# MBUSadapter.net
KiCad netlist of a schematic drawn in EAGLE
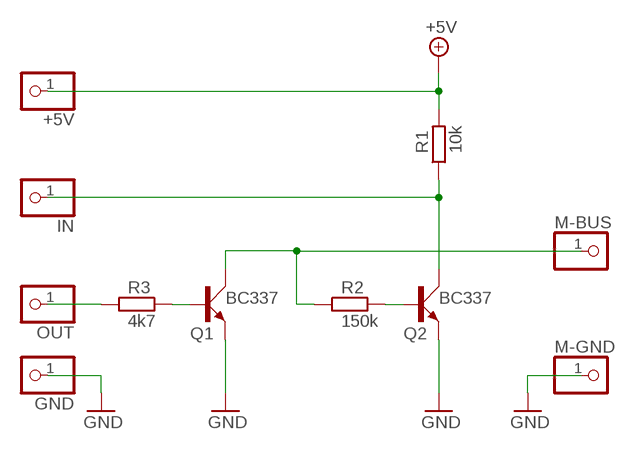
[diagram p0: schematic, sheet 1]

(export (version "E")
  (design (tool "Eeschema 10.0.6"))
  (components
    (comp (ref "+5V")
      (value "PINHD-1X1")
      (footprint "eagle-import:1X01")
      (libsource (lib "eagle-import") (part "PINHD-1X1"))
    )
    (comp (ref "GND")
      (value "PINHD-1X1")
      (footprint "eagle-import:1X01")
      (libsource (lib "eagle-import") (part "PINHD-1X1"))
    )
    (comp (ref "IN")
      (value "PINHD-1X1")
      (footprint "eagle-import:1X01")
      (libsource (lib "eagle-import") (part "PINHD-1X1"))
    )
    (comp (ref "M-BUS")
      (value "PINHD-1X1")
      (footprint "eagle-import:1X01")
      (libsource (lib "eagle-import") (part "PINHD-1X1"))
    )
    (comp (ref "M-GND")
      (value "PINHD-1X1")
      (footprint "eagle-import:1X01")
      (libsource (lib "eagle-import") (part "PINHD-1X1"))
    )
    (comp (ref "OUT")
      (value "PINHD-1X1")
      (footprint "eagle-import:1X01")
      (libsource (lib "eagle-import") (part "PINHD-1X1"))
    )
    (comp (ref "Q1")
      (value "BC337")
      (footprint "eagle-import:SOT54A")
      (libsource (lib "eagle-import") (part "BC337"))
    )
    (comp (ref "Q2")
      (value "BC337")
      (footprint "eagle-import:SOT54A")
      (libsource (lib "eagle-import") (part "BC337"))
    )
    (comp (ref "R1")
      (value "10k")
      (footprint "eagle-import:0207_10")
      (libsource (lib "eagle-import") (part "R-EU_0207/10"))
    )
    (comp (ref "R2")
      (value "150k")
      (footprint "eagle-import:0207_10")
      (libsource (lib "eagle-import") (part "R-EU_0207/10"))
    )
    (comp (ref "R3")
      (value "4k7")
      (footprint "eagle-import:0207_10")
      (libsource (lib "eagle-import") (part "R-EU_0207/10"))
    )
  )
  (nets
    (net (code "1") (name "+5V") (class "Default")
      (node (ref "+5V") (pin "1") (pinfunction "1_1") (pintype "passive"))
      (node (ref "R1") (pin "2") (pinfunction "2_2") (pintype "passive"))
    )
    (net (code "2") (name "GND") (class "Default")
      (node (ref "GND") (pin "1") (pinfunction "1_1") (pintype "passive"))
      (node (ref "M-GND") (pin "1") (pinfunction "1_1") (pintype "passive"))
      (node (ref "Q1") (pin "E") (pinfunction "E_E") (pintype "passive"))
      (node (ref "Q2") (pin "E") (pinfunction "E_E") (pintype "passive"))
    )
    (net (code "3") (name "Net-(IN-Pad1)") (class "Default")
      (node (ref "IN") (pin "1") (pinfunction "1_1") (pintype "passive"))
      (node (ref "Q2") (pin "C") (pinfunction "C_C") (pintype "passive"))
      (node (ref "R1") (pin "1") (pinfunction "1_1") (pintype "passive"))
    )
    (net (code "4") (name "Net-(M-BUS-Pad1)") (class "Default")
      (node (ref "M-BUS") (pin "1") (pinfunction "1_1") (pintype "passive"))
      (node (ref "Q1") (pin "C") (pinfunction "C_C") (pintype "passive"))
      (node (ref "R2") (pin "1") (pinfunction "1_1") (pintype "passive"))
    )
    (net (code "5") (name "Net-(OUT-Pad1)") (class "Default")
      (node (ref "OUT") (pin "1") (pinfunction "1_1") (pintype "passive"))
      (node (ref "R3") (pin "2") (pinfunction "2_2") (pintype "passive"))
    )
    (net (code "6") (name "Net-(Q1-PadB)") (class "Default")
      (node (ref "Q1") (pin "B") (pinfunction "B_B") (pintype "passive"))
      (node (ref "R3") (pin "1") (pinfunction "1_1") (pintype "passive"))
    )
    (net (code "7") (name "Net-(Q2-PadB)") (class "Default")
      (node (ref "Q2") (pin "B") (pinfunction "B_B") (pintype "passive"))
      (node (ref "R2") (pin "2") (pinfunction "2_2") (pintype "passive"))
    )
  )
)
